# SCH_LED-Chaser-Circuit_2025-10-31.net
KiCad netlist of a schematic drawn in EasyEDA
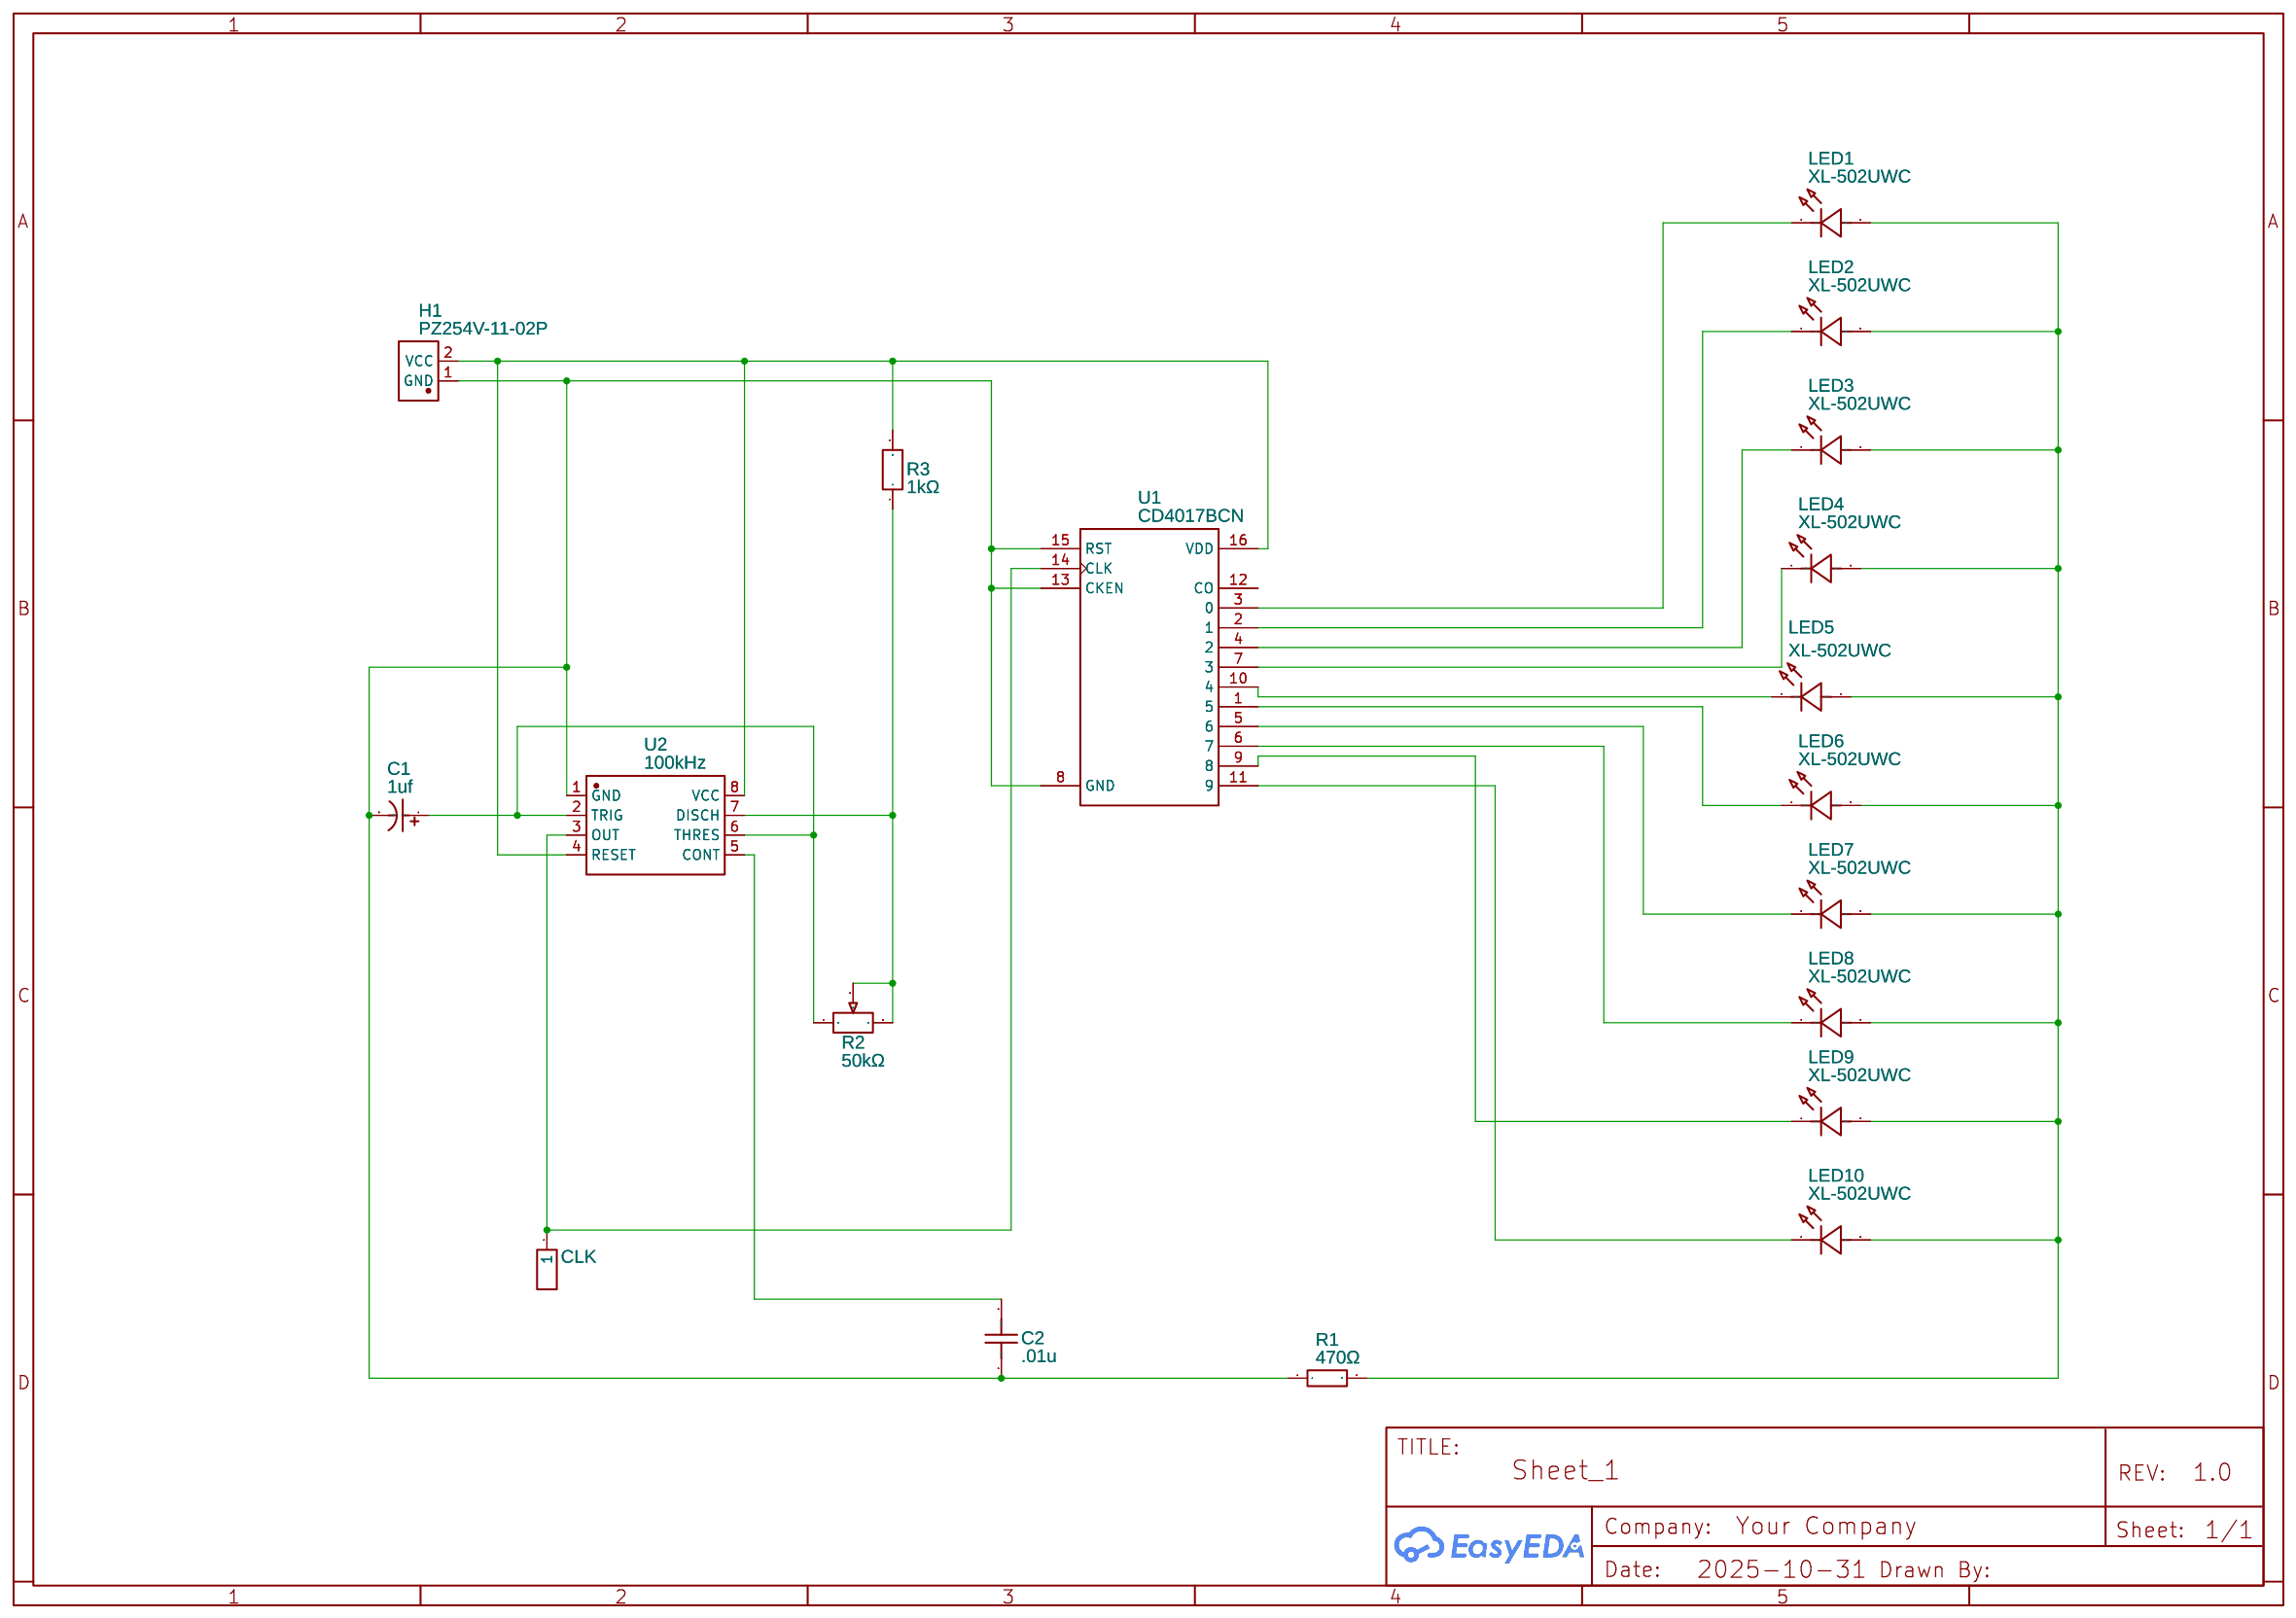
[diagram p0: schematic sheet]

(export (version "E")
  (design (tool "Eeschema 10.0.6"))
  (components
    (comp (ref "C1")
      (value "1uf")
      (fields (field (name "Manufacturer Part") "KF010M050C110A") (field (name "Manufacturer") "CapXon(丰宾)"))
      (libsource (lib "") (part "KF010M050C110A"))
    )
    (comp (ref "C2")
      (value ".01u")
      (fields (field (name "Manufacturer Part") "N09F1B103MN0B0S0N0") (field (name "Manufacturer") "STE(松田)"))
      (libsource (lib "") (part "N09F1B103MN0B0S0N0"))
    )
    (comp (ref "CLK")
      (value "CLK")
      (fields (field (name "Manufacturer Part") "2.54-1*1P针") (field (name "Manufacturer") "BOOMELE(博穆精密)"))
      (libsource (lib "") (part "Header-Male-2.54_1x1"))
    )
    (comp (ref "H1")
      (value "PZ254V-11-02P")
      (fields (field (name "Manufacturer") "XFCN(兴飞)"))
      (libsource (lib "") (part "PZ254V-11-02P"))
    )
    (comp (ref "LED1")
      (value "XL-502UWC")
      (fields (field (name "Manufacturer") "XINGLIGHT(成兴光)"))
      (libsource (lib "") (part "XL-502UWC"))
    )
    (comp (ref "LED2")
      (value "XL-502UWC")
      (fields (field (name "Manufacturer") "XINGLIGHT(成兴光)"))
      (libsource (lib "") (part "XL-502UWC"))
    )
    (comp (ref "LED3")
      (value "XL-502UWC")
      (fields (field (name "Manufacturer") "XINGLIGHT(成兴光)"))
      (libsource (lib "") (part "XL-502UWC"))
    )
    (comp (ref "LED4")
      (value "XL-502UWC")
      (fields (field (name "Manufacturer") "XINGLIGHT(成兴光)"))
      (libsource (lib "") (part "XL-502UWC"))
    )
    (comp (ref "LED5")
      (value "XL-502UWC")
      (fields (field (name "Manufacturer") "XINGLIGHT(成兴光)"))
      (libsource (lib "") (part "XL-502UWC"))
    )
    (comp (ref "LED6")
      (value "XL-502UWC")
      (fields (field (name "Manufacturer") "XINGLIGHT(成兴光)"))
      (libsource (lib "") (part "XL-502UWC"))
    )
    (comp (ref "LED7")
      (value "XL-502UWC")
      (fields (field (name "Manufacturer") "XINGLIGHT(成兴光)"))
      (libsource (lib "") (part "XL-502UWC"))
    )
    (comp (ref "LED8")
      (value "XL-502UWC")
      (fields (field (name "Manufacturer") "XINGLIGHT(成兴光)"))
      (libsource (lib "") (part "XL-502UWC"))
    )
    (comp (ref "LED9")
      (value "XL-502UWC")
      (fields (field (name "Manufacturer") "XINGLIGHT(成兴光)"))
      (libsource (lib "") (part "XL-502UWC"))
    )
    (comp (ref "LED10")
      (value "XL-502UWC")
      (fields (field (name "Manufacturer") "XINGLIGHT(成兴光)"))
      (libsource (lib "") (part "XL-502UWC"))
    )
    (comp (ref "R1")
      (value "470Ω")
      (fields
        (field (name "Manufacturer Part") "MFR0W4F4700A50")
        (field (name "Manufacturer") "UNI-ROYAL(厚声)")
      )
      (libsource (lib "") (part "MFR0W4F4700A50"))
    )
    (comp (ref "R2")
      (value "50kΩ")
      (fields (field (name "Manufacturer Part") "3296X-1-503") (field (name "Manufacturer") "BOCHEN(博晨)"))
      (libsource (lib "") (part "3296X-1-503_C118912"))
    )
    (comp (ref "R3")
      (value "1kΩ")
      (fields (field (name "Manufacturer Part") "MF1/4W-1KΩ±1%T52") (field (name "Manufacturer") "华星机电"))
      (libsource (lib "") (part "MF1/4W-1KΩ±1%T52"))
    )
    (comp (ref "U1") (value "CD4017BCN") (libsource (lib "") (part "CD4017BCN")))
    (comp (ref "U2")
      (value "100kHz")
      (fields (field (name "Manufacturer Part") "NE555P") (field (name "Manufacturer") "TI(德州仪器)"))
      (libsource (lib "") (part "NE555P"))
    )
  )
  (nets
    (net (code "1") (name "Net-(H1-GND)") (class "Default")
      (node (ref "C1") (pin "2") (pinfunction "2_2") (pintype "input"))
      (node (ref "C2") (pin "1") (pinfunction "1_1") (pintype "unspecified"))
      (node (ref "H1") (pin "1") (pinfunction "GND_1") (pintype "unspecified"))
      (node (ref "R1") (pin "1") (pinfunction "1_1") (pintype "input"))
      (node (ref "U1") (pin "13") (pinfunction "CKEN_13") (pintype "unspecified"))
      (node (ref "U1") (pin "15") (pinfunction "RST_15") (pintype "unspecified"))
      (node (ref "U1") (pin "8") (pinfunction "GND_8") (pintype "passive"))
      (node (ref "U2") (pin "1") (pinfunction "GND_1") (pintype "unspecified"))
    )
    (net (code "2") (name "Net-(H1-VCC)") (class "Default")
      (node (ref "H1") (pin "2") (pinfunction "VCC_2") (pintype "unspecified"))
      (node (ref "R3") (pin "2") (pinfunction "2_2") (pintype "unspecified"))
      (node (ref "U1") (pin "16") (pinfunction "VDD_16") (pintype "passive"))
      (node (ref "U2") (pin "4") (pinfunction "RESET_4") (pintype "unspecified"))
      (node (ref "U2") (pin "8") (pinfunction "VCC_8") (pintype "unspecified"))
    )
    (net (code "3") (name "Net-(LED1-A)") (class "Default")
      (node (ref "LED1") (pin "2") (pinfunction "A_2") (pintype "unspecified"))
      (node (ref "LED10") (pin "2") (pinfunction "A_2") (pintype "unspecified"))
      (node (ref "LED2") (pin "2") (pinfunction "A_2") (pintype "unspecified"))
      (node (ref "LED3") (pin "2") (pinfunction "A_2") (pintype "unspecified"))
      (node (ref "LED4") (pin "2") (pinfunction "A_2") (pintype "unspecified"))
      (node (ref "LED5") (pin "2") (pinfunction "A_2") (pintype "unspecified"))
      (node (ref "LED6") (pin "2") (pinfunction "A_2") (pintype "unspecified"))
      (node (ref "LED7") (pin "2") (pinfunction "A_2") (pintype "unspecified"))
      (node (ref "LED8") (pin "2") (pinfunction "A_2") (pintype "unspecified"))
      (node (ref "LED9") (pin "2") (pinfunction "A_2") (pintype "unspecified"))
      (node (ref "R1") (pin "2") (pinfunction "2_2") (pintype "input"))
    )
    (net (code "4") (name "Net-(LED1-K)") (class "Default")
      (node (ref "LED1") (pin "1") (pinfunction "K_1") (pintype "unspecified"))
      (node (ref "U1") (pin "3") (pinfunction "0_3") (pintype "output"))
    )
    (net (code "5") (name "Net-(LED2-K)") (class "Default")
      (node (ref "LED2") (pin "1") (pinfunction "K_1") (pintype "unspecified"))
      (node (ref "U1") (pin "2") (pinfunction "1_2") (pintype "output"))
    )
    (net (code "6") (name "Net-(LED3-K)") (class "Default")
      (node (ref "LED3") (pin "1") (pinfunction "K_1") (pintype "unspecified"))
      (node (ref "U1") (pin "4") (pinfunction "2_4") (pintype "output"))
    )
    (net (code "7") (name "Net-(LED4-K)") (class "Default")
      (node (ref "LED4") (pin "1") (pinfunction "K_1") (pintype "unspecified"))
      (node (ref "U1") (pin "7") (pinfunction "3_7") (pintype "output"))
    )
    (net (code "8") (name "Net-(LED5-K)") (class "Default")
      (node (ref "LED5") (pin "1") (pinfunction "K_1") (pintype "unspecified"))
      (node (ref "U1") (pin "10") (pinfunction "4_10") (pintype "output"))
    )
    (net (code "9") (name "Net-(LED6-K)") (class "Default")
      (node (ref "LED6") (pin "1") (pinfunction "K_1") (pintype "unspecified"))
      (node (ref "U1") (pin "1") (pinfunction "5_1") (pintype "output"))
    )
    (net (code "10") (name "Net-(LED7-K)") (class "Default")
      (node (ref "LED7") (pin "1") (pinfunction "K_1") (pintype "unspecified"))
      (node (ref "U1") (pin "5") (pinfunction "6_5") (pintype "output"))
    )
    (net (code "11") (name "Net-(LED8-K)") (class "Default")
      (node (ref "LED8") (pin "1") (pinfunction "K_1") (pintype "unspecified"))
      (node (ref "U1") (pin "6") (pinfunction "7_6") (pintype "output"))
    )
    (net (code "12") (name "Net-(LED9-K)") (class "Default")
      (node (ref "LED9") (pin "1") (pinfunction "K_1") (pintype "unspecified"))
      (node (ref "U1") (pin "9") (pinfunction "8_9") (pintype "output"))
    )
    (net (code "13") (name "Net-(LED10-K)") (class "Default")
      (node (ref "LED10") (pin "1") (pinfunction "K_1") (pintype "unspecified"))
      (node (ref "U1") (pin "11") (pinfunction "9_11") (pintype "output"))
    )
    (net (code "14") (name "Net-(U1-CLK)") (class "Default")
      (node (ref "CLK") (pin "1") (pinfunction "1_1") (pintype "input"))
      (node (ref "U1") (pin "14") (pinfunction "CLK_14") (pintype "unspecified"))
      (node (ref "U2") (pin "3") (pinfunction "OUT_3") (pintype "unspecified"))
    )
    (net (code "15") (name "Net-(U2-CONT)") (class "Default")
      (node (ref "C2") (pin "2") (pinfunction "2_2") (pintype "unspecified"))
      (node (ref "U2") (pin "5") (pinfunction "CONT_5") (pintype "unspecified"))
    )
    (net (code "16") (name "Net-(U2-DISCH)") (class "Default")
      (node (ref "R2") (pin "2") (pinfunction "2_2") (pintype "input"))
      (node (ref "R2") (pin "3") (pinfunction "3_3") (pintype "input"))
      (node (ref "R3") (pin "1") (pinfunction "1_1") (pintype "unspecified"))
      (node (ref "U2") (pin "7") (pinfunction "DISCH_7") (pintype "unspecified"))
    )
    (net (code "17") (name "Net-(U2-THRES)") (class "Default")
      (node (ref "C1") (pin "1") (pinfunction "1_1") (pintype "input"))
      (node (ref "R2") (pin "1") (pinfunction "1_1") (pintype "input"))
      (node (ref "U2") (pin "2") (pinfunction "TRIG_2") (pintype "unspecified"))
      (node (ref "U2") (pin "6") (pinfunction "THRES_6") (pintype "unspecified"))
    )
    (net (code "18") (name "unconnected-(U1-CO-Pad12)") (class "Default")
      (node (ref "U1") (pin "12") (pinfunction "CO_12") (pintype "output"))
    )
  )
)
